# 3V3_BUCK.net
KiCad netlist of a schematic drawn in Altium Designer
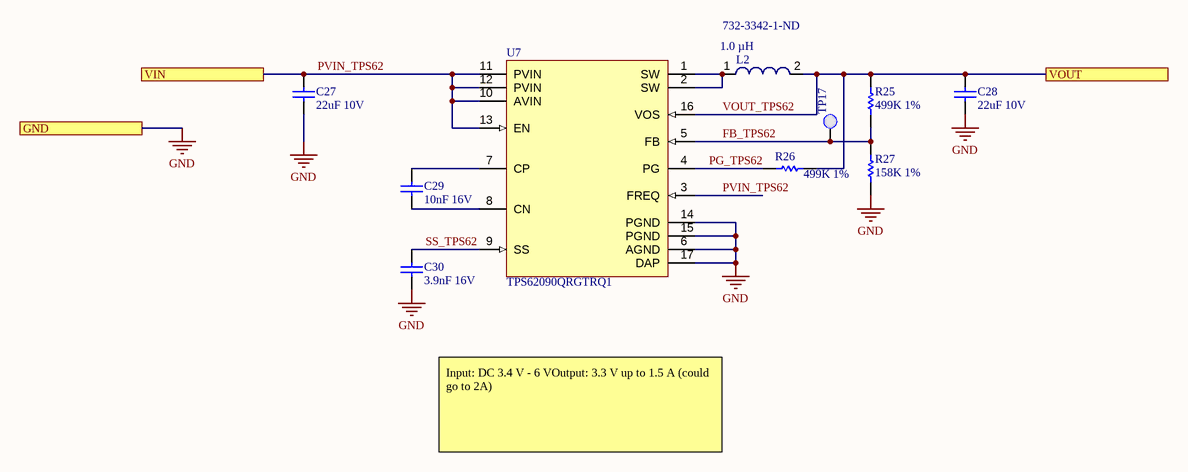
[diagram p0: 3V3_BUCK.SchDoc]

(export (version "E")
  (design (tool "Eeschema 10.0.6"))
  (components
    (comp (ref "C27")
      (value "22uF 10V")
      (footprint "CAPC0805(2012)145_N")
      (description "CAP 22uF 10V ±20% 0805 (2012 Metric) Thickness 1.45mm SMD")
      (fields (field (name "TOLERANCE") "Â±20%"))
      (libsource (lib "Altium Content Vault") (part "CAP"))
    )
    (comp (ref "C28")
      (value "22uF 10V")
      (footprint "CAPC0805(2012)145_N")
      (description "CAP 22uF 10V ±20% 0805 (2012 Metric) Thickness 1.45mm SMD")
      (fields (field (name "TOLERANCE") "Â±20%"))
      (libsource (lib "Altium Content Vault") (part "CAP"))
    )
    (comp (ref "C29")
      (value "10nF 16V")
      (footprint "CAPC0603(1608)100_N")
      (description "CAP 10nF 16V ±10% 0603 (1608 Metric) Thickness 1mm SMD")
      (fields (field (name "TOLERANCE") "Â±10%"))
      (libsource (lib "Altium Content Vault") (part "CAP"))
    )
    (comp (ref "C30")
      (value "3.9nF 16V")
      (footprint "CAPC0603(1608)100_N")
      (description "CAP 3.9nF 16V ±10% 0603 (1608 Metric) Thickness 1mm SMD")
      (fields (field (name "TOLERANCE") "Â±10%"))
      (libsource (lib "Altium Content Vault") (part "CAP"))
    )
    (comp (ref "L2")
      (value "74437324010")
      (footprint "WE-LHMI 4020")
      (description "SMD Power Inductor WE-LHMI, L=1.0 µH")
      (fields
        (field (name "INDUCTANCE") "1.0 µH")
        (field (name "MANUFACTURER") "Wuerth Elektronik")
        (field (name "SUPPLIER PART NUMBER 1") "732-3342-1-ND")
        (field (name "TOLERANCE") "20%")
      )
      (libsource (lib "Altium Content Vault") (part "WE-IND-INDUCTOR-2"))
    )
    (comp (ref "R25")
      (value "499K 1%")
      (footprint "RESC0603(1608)_L")
      (description "499K 0.1W 1% 0603 (1608 Metric)  SMD")
      (fields (field (name "TOLERANCE") "1 %") (field (name "POWER") "0.1 W"))
      (libsource (lib "Altium Content Vault") (part "RES"))
    )
    (comp (ref "R26")
      (value "499K 1%")
      (footprint "RESC0603(1608)_L")
      (description "499K 0.1W 1% 0603 (1608 Metric)  SMD")
      (fields (field (name "TOLERANCE") "1 %") (field (name "POWER") "0.1 W"))
      (libsource (lib "Altium Content Vault") (part "RES"))
    )
    (comp (ref "R27")
      (value "158K 1%")
      (footprint "RESC0603(1608)_N")
      (description "158K 0.1W 1% 0603 (1608 Metric)  SMD")
      (fields (field (name "TOLERANCE") "1 %") (field (name "POWER") "0.1 W"))
      (libsource (lib "Altium Content Vault") (part "RES"))
    )
    (comp (ref "TP17")
      (value "0.1\" Pad")
      (footprint "PCBComponent")
      (libsource (lib "Components - 12.02.20 - 18.05") (part "0.1{dblquote} Pad-A.4"))
    )
    (comp (ref "U7")
      (value "TPS62090QRGTRQ1")
      (footprint "FP-RGT0016C-IPC_A")
      (description "IC REG BUCK")
      (fields
        (field (name "MANUFACTURER") "Texas Instruments")
        (field (name "COPYRIGHT") "Copyright (C) 2018 Accelerated Designs. All rights reserved")
      )
      (libsource (lib "2020-02-13_00-03-41") (part "TPS62090QRGTRQ1"))
    )
  )
  (nets
    (net (code "1") (name "/FB_TPS62") (class "Default")
      (node (ref "R25") (pin "1") (pinfunction "1_1") (pintype "passive"))
      (node (ref "R27") (pin "2") (pinfunction "2_2") (pintype "passive"))
      (node (ref "TP17") (pin "1") (pinfunction "PAD_1") (pintype "passive"))
      (node (ref "U7") (pin "5") (pinfunction "FB_5") (pintype "input"))
    )
    (net (code "2") (name "/PG_TPS62") (class "Default")
      (node (ref "R26") (pin "2") (pinfunction "2_2") (pintype "passive"))
      (node (ref "U7") (pin "4") (pinfunction "PG_4") (pintype "open_collector"))
    )
    (net (code "3") (name "/PVIN_TPS62") (class "Default")
      (node (ref "C27") (pin "2") (pinfunction "2_2") (pintype "passive"))
      (node (ref "U7") (pin "10") (pinfunction "AVIN_10") (pintype "power_in"))
      (node (ref "U7") (pin "11") (pinfunction "PVIN_11") (pintype "power_in"))
      (node (ref "U7") (pin "12") (pinfunction "PVIN_12") (pintype "power_in"))
      (node (ref "U7") (pin "13") (pinfunction "EN_13") (pintype "input"))
      (node (ref "U7") (pin "3") (pinfunction "FREQ_3") (pintype "input"))
    )
    (net (code "4") (name "/SS_TPS62") (class "Default")
      (node (ref "C30") (pin "2") (pinfunction "2_2") (pintype "passive"))
      (node (ref "U7") (pin "9") (pinfunction "SS_9") (pintype "input"))
    )
    (net (code "5") (name "/VOUT_TPS62") (class "Default")
      (node (ref "C28") (pin "2") (pinfunction "2_2") (pintype "passive"))
      (node (ref "L2") (pin "2") (pinfunction "2_2") (pintype "passive"))
      (node (ref "R25") (pin "2") (pinfunction "2_2") (pintype "passive"))
      (node (ref "R26") (pin "1") (pinfunction "1_1") (pintype "passive"))
      (node (ref "U7") (pin "16") (pinfunction "VOS_16") (pintype "input"))
    )
    (net (code "6") (name "GND") (class "Default")
      (node (ref "C27") (pin "1") (pinfunction "1_1") (pintype "passive"))
      (node (ref "C28") (pin "1") (pinfunction "1_1") (pintype "passive"))
      (node (ref "C30") (pin "1") (pinfunction "1_1") (pintype "passive"))
      (node (ref "R27") (pin "1") (pinfunction "1_1") (pintype "passive"))
      (node (ref "U7") (pin "14") (pinfunction "PGND_14") (pintype "power_in"))
      (node (ref "U7") (pin "15") (pinfunction "PGND_15") (pintype "power_in"))
      (node (ref "U7") (pin "17") (pinfunction "DAP_17") (pintype "power_in"))
      (node (ref "U7") (pin "6") (pinfunction "AGND_6") (pintype "power_in"))
    )
    (net (code "7") (name "Net-(L2-Pad1)") (class "Default")
      (node (ref "L2") (pin "1") (pinfunction "1_1") (pintype "passive"))
      (node (ref "U7") (pin "1") (pinfunction "SW_1") (pintype "power_in"))
      (node (ref "U7") (pin "2") (pinfunction "SW_2") (pintype "power_in"))
    )
    (net (code "8") (name "Net-(U7-CN)") (class "Default")
      (node (ref "C29") (pin "1") (pinfunction "1_1") (pintype "passive"))
      (node (ref "U7") (pin "8") (pinfunction "CN_8") (pintype "passive"))
    )
    (net (code "9") (name "Net-(U7-CP)") (class "Default")
      (node (ref "C29") (pin "2") (pinfunction "2_2") (pintype "passive"))
      (node (ref "U7") (pin "7") (pinfunction "CP_7") (pintype "passive"))
    )
  )
)
